# Connector_Power.net
KiCad netlist of a schematic drawn in Altium Designer
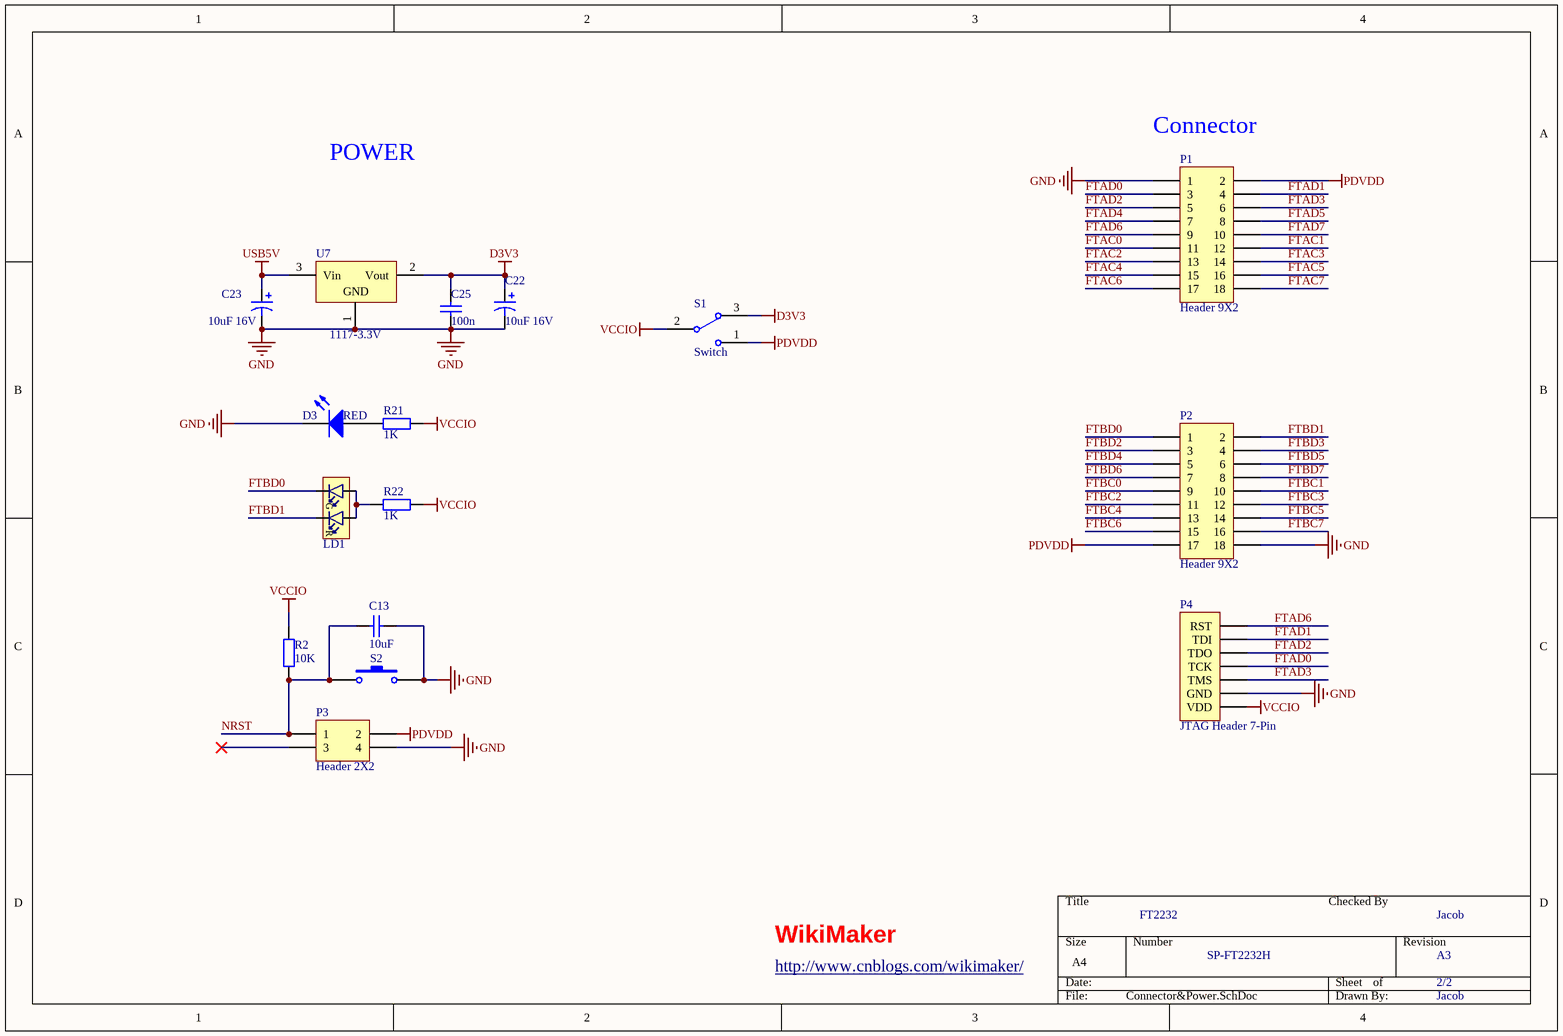
[diagram p0: Connector&Power.SchDoc]

(export (version "E")
  (design (tool "Eeschema 10.0.6"))
  (components
    (comp (ref "C13")
      (value "10uF")
      (footprint "0603L")
      (description "Capacitor")
      (fields (field (name "PUBLISHER") "Altium Limited"))
      (libsource (lib "Miscellaneous Devices") (part "Cap"))
    )
    (comp (ref "C22")
      (value "10uF 16V")
      (footprint "1206")
      (description "Polarized Capacitor (Radial)")
      (fields (field (name "PUBLISHER") "Altium Limited"))
      (libsource (lib "Miscellaneous Devices") (part "Cap Pol1"))
    )
    (comp (ref "C23")
      (value "10uF 16V")
      (footprint "1206")
      (description "Polarized Capacitor (Radial)")
      (fields (field (name "PUBLISHER") "Altium Limited"))
      (libsource (lib "Miscellaneous Devices") (part "Cap Pol1"))
    )
    (comp (ref "C25")
      (value "100n")
      (footprint "0603M")
      (description "Capacitor")
      (fields (field (name "PUBLISHER") "Altium Limited"))
      (libsource (lib "Miscellaneous Devices") (part "Cap"))
    )
    (comp (ref "D3")
      (value "RED")
      (footprint "0603pn")
      (description "Typical INFRARED GaAs LED")
      (fields (field (name "PUBLISHER") "Altium Limited"))
      (libsource (lib "Miscellaneous Devices") (part "LED0"))
    )
    (comp (ref "LD1")
      (value "LTST-C195KGJRKT")
      (footprint "0805-LED-Bi")
      (description "Avago, HSMF-A203 Bi-Color LED")
      (fields
        (field (name "MANUFACTURER") "Lite-On Inc")
        (field (name "2ND SOURCE PART NUMBER") "859-LTST-C195KGJRKT")
        (field (name "PUBLISHER") "Nordic Semiconductor")
      )
      (libsource (lib "Misc") (part "LED-DUAL"))
    )
    (comp (ref "P1")
      (value "Header 9X2")
      (footprint "HDR2X9/2.54MM")
      (description "Header, 9-Pin, Dual row")
      (fields (field (name "PUBLISHER") "Altium Limited"))
      (libsource (lib "Miscellaneous Connectors") (part "Header 9X2"))
    )
    (comp (ref "P2")
      (value "Header 9X2")
      (footprint "HDR2X9/2.54MM")
      (description "Header, 9-Pin, Dual row")
      (fields (field (name "PUBLISHER") "Altium Limited"))
      (libsource (lib "Miscellaneous Connectors") (part "Header 9X2"))
    )
    (comp (ref "P3")
      (value "Header 2X2")
      (footprint "HDR2X2/2.54MM")
      (description "Header, 2-Pin, Dual row")
      (fields (field (name "PUBLISHER") "Altium Limited"))
      (libsource (lib "Miscellaneous Connectors") (part "Header 2X2"))
    )
    (comp (ref "P4")
      (value "JTAG Header 7-Pin")
      (footprint "HDR1X7/2.54MM")
      (description "Header, 7-Pin")
      (fields (field (name "PUBLISHER") "Altium Limited"))
      (libsource (lib "Connector") (part "JTAG Header 7-Pin"))
    )
    (comp (ref "R2")
      (value "10K")
      (footprint "0603L")
      (description "Resistor")
      (fields (field (name "PUBLISHER") "Altium Limited"))
      (libsource (lib "") (part "Res2_1"))
    )
    (comp (ref "R21")
      (value "1K")
      (footprint "0603M")
      (description "Resistor")
      (fields (field (name "PUBLISHER") "Altium Limited"))
      (libsource (lib "Miscellaneous Devices") (part "Res2"))
    )
    (comp (ref "R22")
      (value "1K")
      (footprint "0603M")
      (description "Resistor")
      (fields (field (name "PUBLISHER") "Altium Limited"))
      (libsource (lib "Miscellaneous Devices") (part "Res2"))
    )
    (comp (ref "S1")
      (value "Switch")
      (footprint "HDR1X3/2.54mm")
      (description "SPDT Subminiature Toggle Switch, Right Angle Mounting, Vertical Actuation")
      (fields (field (name "PUBLISHER") "Altium Limited"))
      (libsource (lib "Studio") (part "SW-SPDT"))
    )
    (comp (ref "S2")
      (value "~")
      (footprint "KEY-2x4-SMD")
      (description "Switch")
      (fields (field (name "PUBLISHER") "Altium Limited"))
      (libsource (lib "Miscellaneous Devices") (part "SW-PB"))
    )
    (comp (ref "U7")
      (value "1117-3.3V")
      (footprint "SOT-223")
      (description "1117- 3.3 2.5 1.8")
      (fields (field (name "PUBLISHER") "Altium Limited"))
      (libsource (lib "Studio") (part "1117"))
    )
  )
  (nets
    (net (code "1") (name "/FTAC0") (class "Default")
      (node (ref "P1") (pin "11") (pinfunction "11_11") (pintype "passive"))
    )
    (net (code "2") (name "/FTAC1") (class "Default")
      (node (ref "P1") (pin "12") (pinfunction "12_12") (pintype "passive"))
    )
    (net (code "3") (name "/FTAC2") (class "Default")
      (node (ref "P1") (pin "13") (pinfunction "13_13") (pintype "passive"))
    )
    (net (code "4") (name "/FTAC3") (class "Default")
      (node (ref "P1") (pin "14") (pinfunction "14_14") (pintype "passive"))
    )
    (net (code "5") (name "/FTAC4") (class "Default")
      (node (ref "P1") (pin "15") (pinfunction "15_15") (pintype "passive"))
    )
    (net (code "6") (name "/FTAC5") (class "Default")
      (node (ref "P1") (pin "16") (pinfunction "16_16") (pintype "passive"))
    )
    (net (code "7") (name "/FTAC6") (class "Default")
      (node (ref "P1") (pin "17") (pinfunction "17_17") (pintype "passive"))
    )
    (net (code "8") (name "/FTAC7") (class "Default")
      (node (ref "P1") (pin "18") (pinfunction "18_18") (pintype "passive"))
    )
    (net (code "9") (name "/FTAD0") (class "Default")
      (node (ref "P1") (pin "3") (pinfunction "3_3") (pintype "passive"))
      (node (ref "P4") (pin "4") (pinfunction "TCK_4") (pintype "passive"))
    )
    (net (code "10") (name "/FTAD1") (class "Default")
      (node (ref "P1") (pin "4") (pinfunction "4_4") (pintype "passive"))
      (node (ref "P4") (pin "6") (pinfunction "TDI_6") (pintype "passive"))
    )
    (net (code "11") (name "/FTAD2") (class "Default")
      (node (ref "P1") (pin "5") (pinfunction "5_5") (pintype "passive"))
      (node (ref "P4") (pin "5") (pinfunction "TDO_5") (pintype "passive"))
    )
    (net (code "12") (name "/FTAD3") (class "Default")
      (node (ref "P1") (pin "6") (pinfunction "6_6") (pintype "passive"))
      (node (ref "P4") (pin "3") (pinfunction "TMS_3") (pintype "passive"))
    )
    (net (code "13") (name "/FTAD4") (class "Default")
      (node (ref "P1") (pin "7") (pinfunction "7_7") (pintype "passive"))
    )
    (net (code "14") (name "/FTAD5") (class "Default")
      (node (ref "P1") (pin "8") (pinfunction "8_8") (pintype "passive"))
    )
    (net (code "15") (name "/FTAD6") (class "Default")
      (node (ref "P1") (pin "9") (pinfunction "9_9") (pintype "passive"))
      (node (ref "P4") (pin "7") (pinfunction "RST_7") (pintype "passive"))
    )
    (net (code "16") (name "/FTAD7") (class "Default")
      (node (ref "P1") (pin "10") (pinfunction "10_10") (pintype "passive"))
    )
    (net (code "17") (name "/FTBC0") (class "Default")
      (node (ref "P2") (pin "9") (pinfunction "9_9") (pintype "passive"))
    )
    (net (code "18") (name "/FTBC1") (class "Default")
      (node (ref "P2") (pin "10") (pinfunction "10_10") (pintype "passive"))
    )
    (net (code "19") (name "/FTBC2") (class "Default")
      (node (ref "P2") (pin "11") (pinfunction "11_11") (pintype "passive"))
    )
    (net (code "20") (name "/FTBC3") (class "Default")
      (node (ref "P2") (pin "12") (pinfunction "12_12") (pintype "passive"))
    )
    (net (code "21") (name "/FTBC4") (class "Default")
      (node (ref "P2") (pin "13") (pinfunction "13_13") (pintype "passive"))
    )
    (net (code "22") (name "/FTBC5") (class "Default")
      (node (ref "P2") (pin "14") (pinfunction "14_14") (pintype "passive"))
    )
    (net (code "23") (name "/FTBC6") (class "Default")
      (node (ref "P2") (pin "15") (pinfunction "15_15") (pintype "passive"))
    )
    (net (code "24") (name "/FTBC7") (class "Default")
      (node (ref "P2") (pin "16") (pinfunction "16_16") (pintype "passive"))
    )
    (net (code "25") (name "/FTBD0") (class "Default")
      (node (ref "LD1") (pin "1") (pinfunction "C1_1") (pintype "passive"))
      (node (ref "P2") (pin "1") (pinfunction "1_1") (pintype "passive"))
    )
    (net (code "26") (name "/FTBD1") (class "Default")
      (node (ref "LD1") (pin "2") (pinfunction "C2_2") (pintype "passive"))
      (node (ref "P2") (pin "2") (pinfunction "2_2") (pintype "passive"))
    )
    (net (code "27") (name "/FTBD2") (class "Default")
      (node (ref "P2") (pin "3") (pinfunction "3_3") (pintype "passive"))
    )
    (net (code "28") (name "/FTBD3") (class "Default")
      (node (ref "P2") (pin "4") (pinfunction "4_4") (pintype "passive"))
    )
    (net (code "29") (name "/FTBD4") (class "Default")
      (node (ref "P2") (pin "5") (pinfunction "5_5") (pintype "passive"))
    )
    (net (code "30") (name "/FTBD5") (class "Default")
      (node (ref "P2") (pin "6") (pinfunction "6_6") (pintype "passive"))
    )
    (net (code "31") (name "/FTBD6") (class "Default")
      (node (ref "P2") (pin "7") (pinfunction "7_7") (pintype "passive"))
    )
    (net (code "32") (name "/FTBD7") (class "Default")
      (node (ref "P2") (pin "8") (pinfunction "8_8") (pintype "passive"))
    )
    (net (code "33") (name "/NRST") (class "Default")
      (node (ref "C13") (pin "2") (pinfunction "2_2") (pintype "passive"))
      (node (ref "P3") (pin "1") (pinfunction "1_1") (pintype "passive"))
      (node (ref "R2") (pin "2") (pinfunction "2_2") (pintype "passive"))
      (node (ref "S2") (pin "2") (pinfunction "2_2") (pintype "passive"))
    )
    (net (code "34") (name "D3V3") (class "Default")
      (node (ref "C22") (pin "1") (pinfunction "1_1") (pintype "passive"))
      (node (ref "C25") (pin "2") (pinfunction "2_2") (pintype "passive"))
      (node (ref "S1") (pin "3") (pinfunction "3_3") (pintype "passive"))
      (node (ref "U7") (pin "2") (pinfunction "Vout_2") (pintype "passive"))
    )
    (net (code "35") (name "GND") (class "Default")
      (node (ref "C13") (pin "1") (pinfunction "1_1") (pintype "passive"))
      (node (ref "C22") (pin "2") (pinfunction "2_2") (pintype "passive"))
      (node (ref "C23") (pin "2") (pinfunction "2_2") (pintype "passive"))
      (node (ref "C25") (pin "1") (pinfunction "1_1") (pintype "passive"))
      (node (ref "D3") (pin "2") (pinfunction "K_2") (pintype "passive"))
      (node (ref "P1") (pin "1") (pinfunction "1_1") (pintype "passive"))
      (node (ref "P2") (pin "18") (pinfunction "18_18") (pintype "passive"))
      (node (ref "P3") (pin "4") (pinfunction "4_4") (pintype "passive"))
      (node (ref "P4") (pin "2") (pinfunction "GND_2") (pintype "passive"))
      (node (ref "S2") (pin "1") (pinfunction "1_1") (pintype "passive"))
      (node (ref "U7") (pin "1") (pinfunction "GND/ADJUST_1") (pintype "passive"))
    )
    (net (code "36") (name "Net-(D3-A)") (class "Default")
      (node (ref "D3") (pin "1") (pinfunction "A_1") (pintype "passive"))
      (node (ref "R21") (pin "2") (pinfunction "2_2") (pintype "passive"))
    )
    (net (code "37") (name "Net-(LD1-A1)") (class "Default")
      (node (ref "LD1") (pin "3") (pinfunction "A2_3") (pintype "passive"))
      (node (ref "LD1") (pin "4") (pinfunction "A1_4") (pintype "passive"))
      (node (ref "R22") (pin "2") (pinfunction "2_2") (pintype "passive"))
    )
    (net (code "38") (name "PDVDD") (class "Default")
      (node (ref "P1") (pin "2") (pinfunction "2_2") (pintype "passive"))
      (node (ref "P2") (pin "17") (pinfunction "17_17") (pintype "passive"))
      (node (ref "P3") (pin "2") (pinfunction "2_2") (pintype "passive"))
      (node (ref "S1") (pin "1") (pinfunction "1_1") (pintype "passive"))
    )
    (net (code "39") (name "USB5V") (class "Default")
      (node (ref "C23") (pin "1") (pinfunction "1_1") (pintype "passive"))
      (node (ref "U7") (pin "3") (pinfunction "Vin_3") (pintype "passive"))
    )
    (net (code "40") (name "VCCIO") (class "Default")
      (node (ref "P4") (pin "1") (pinfunction "VDD_1") (pintype "passive"))
      (node (ref "R2") (pin "1") (pinfunction "1_1") (pintype "passive"))
      (node (ref "R21") (pin "1") (pinfunction "1_1") (pintype "passive"))
      (node (ref "R22") (pin "1") (pinfunction "1_1") (pintype "passive"))
      (node (ref "S1") (pin "2") (pinfunction "2_2") (pintype "passive"))
    )
    (net (code "41") (name "unconnected-(P3-Pad3)") (class "Default")
      (node (ref "P3") (pin "3") (pinfunction "3_3") (pintype "passive+no_connect"))
    )
  )
)
